# TSL2561_Luminosity_Sensor_Breakout_V01.net
KiCad netlist of a schematic drawn in EAGLE
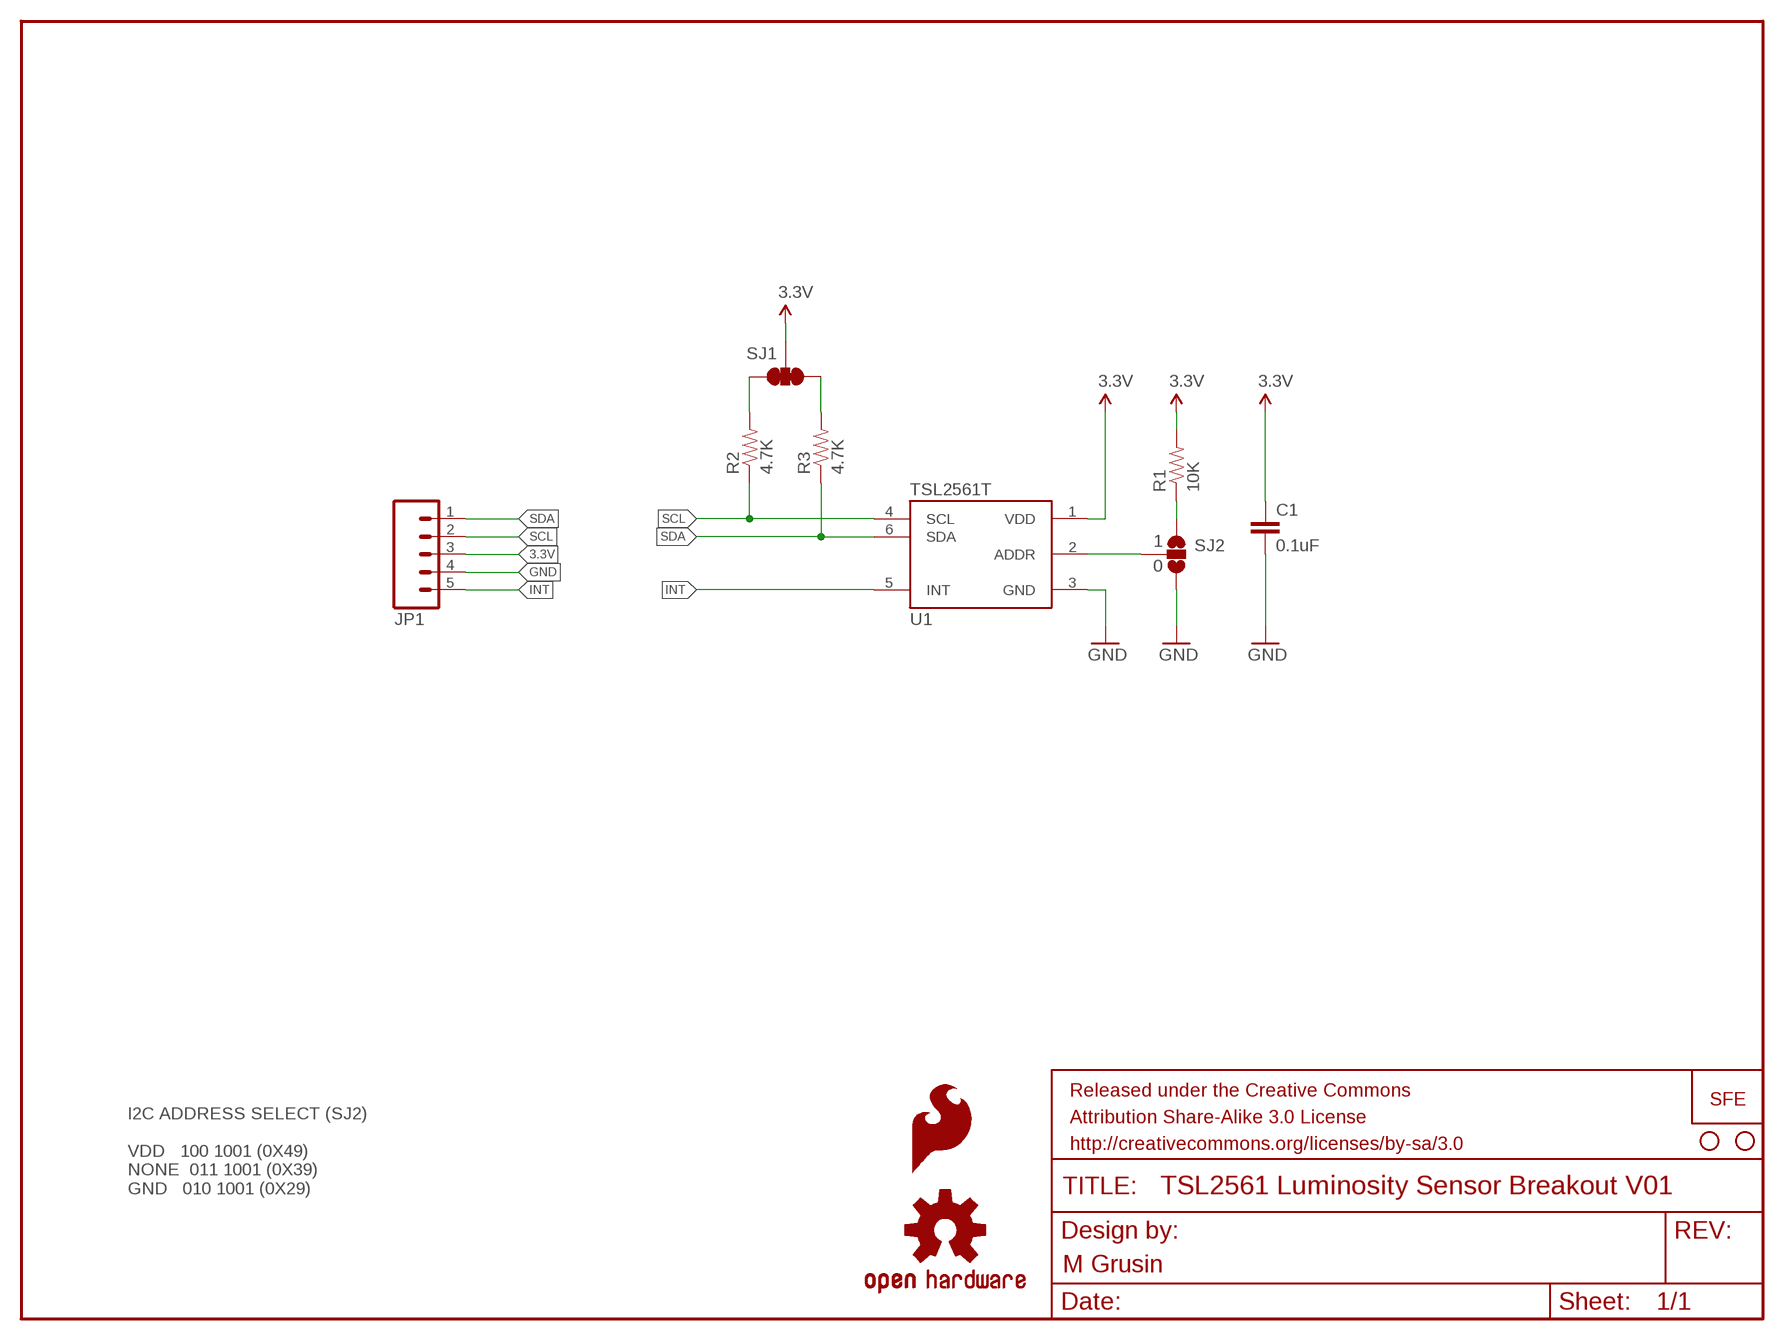
[diagram p0: schematic, sheet 1]

(export (version "E")
  (design (tool "Eeschema 10.0.6"))
  (components
    (comp (ref "C1")
      (value "0.1uF")
      (footprint "eagle-import:0603-CAP")
      (libsource (lib "eagle-import") (part "CAP0603-CAP"))
    )
    (comp (ref "FRAME1")
      (value "FRAME-LETTER")
      (footprint "eagle-import:CREATIVE_COMMONS")
      (libsource (lib "eagle-import") (part "FRAME-LETTER"))
    )
    (comp (ref "JP1")
      (value "M05_ROUNDONLY_NOSILK")
      (footprint "eagle-import:1X05_ROUNDONLY_NOSILK")
      (libsource (lib "eagle-import") (part "M05_ROUNDONLY_NOSILK"))
    )
    (comp (ref "LOGO1")
      (value "OSHW-LOGOS")
      (footprint "eagle-import:OSHW-LOGO-S")
      (libsource (lib "eagle-import") (part "OSHW-LOGOS"))
    )
    (comp (ref "LOGO2")
      (value "LOGO-SFENW2")
      (footprint "eagle-import:SFE-NEW-WEB")
      (libsource (lib "eagle-import") (part "LOGO-SFENW2"))
    )
    (comp (ref "LOGO3")
      (value "SFE_LOGO_FLAME.1_INCH")
      (footprint "eagle-import:SFE_LOGO_FLAME_.1")
      (libsource (lib "eagle-import") (part "SFE_LOGO_FLAME.1_INCH"))
    )
    (comp (ref "R1")
      (value "10K")
      (footprint "eagle-import:0603-RES")
      (libsource (lib "eagle-import") (part "RESISTOR0603"))
    )
    (comp (ref "R2")
      (value "4.7K")
      (footprint "eagle-import:0603-RES")
      (libsource (lib "eagle-import") (part "RESISTOR0603"))
    )
    (comp (ref "R3")
      (value "4.7K")
      (footprint "eagle-import:0603-RES")
      (libsource (lib "eagle-import") (part "RESISTOR0603"))
    )
    (comp (ref "SJ1")
      (value "SOLDERJUMPER_2WAYPASTE1&2&3")
      (footprint "eagle-import:SJ_3_PASTE1&2&3")
      (libsource (lib "eagle-import") (part "SOLDERJUMPER_2WAYPASTE1&2&3"))
    )
    (comp (ref "SJ2")
      (value "SOLDERJUMPER_2WAYS")
      (footprint "eagle-import:SJ_3")
      (libsource (lib "eagle-import") (part "SOLDERJUMPER_2WAYS"))
    )
    (comp (ref "STANDOFF1")
      (value "STAND-OFF")
      (footprint "eagle-import:STAND-OFF")
      (libsource (lib "eagle-import") (part "STAND-OFF"))
    )
    (comp (ref "STANDOFF2")
      (value "STAND-OFF")
      (footprint "eagle-import:STAND-OFF")
      (libsource (lib "eagle-import") (part "STAND-OFF"))
    )
    (comp (ref "U1")
      (value "TSL2561T")
      (footprint "eagle-import:TMB-6")
      (libsource (lib "eagle-import") (part "TSL2561T"))
    )
  )
  (nets
    (net (code "1") (name "3.3V") (class "Default")
      (node (ref "C1") (pin "1") (pinfunction "1_1") (pintype "passive"))
      (node (ref "JP1") (pin "3") (pinfunction "3_3") (pintype "passive"))
      (node (ref "R1") (pin "2") (pinfunction "2_2") (pintype "passive"))
      (node (ref "SJ1") (pin "2") (pinfunction "2_2") (pintype "passive"))
      (node (ref "U1") (pin "1") (pinfunction "VDD_1") (pintype "power_in"))
    )
    (net (code "2") (name "GND") (class "Default")
      (node (ref "C1") (pin "2") (pinfunction "2_2") (pintype "passive"))
      (node (ref "JP1") (pin "4") (pinfunction "4_4") (pintype "passive"))
      (node (ref "SJ2") (pin "3") (pinfunction "3_3") (pintype "passive"))
      (node (ref "U1") (pin "3") (pinfunction "GND_3") (pintype "power_in"))
    )
    (net (code "3") (name "INT") (class "Default")
      (node (ref "JP1") (pin "5") (pinfunction "5_5") (pintype "passive"))
      (node (ref "U1") (pin "5") (pinfunction "INT_5") (pintype "output"))
    )
    (net (code "4") (name "Net-(R1-Pad1)") (class "Default")
      (node (ref "R1") (pin "1") (pinfunction "1_1") (pintype "passive"))
      (node (ref "SJ2") (pin "1") (pinfunction "1_1") (pintype "passive"))
    )
    (net (code "5") (name "Net-(R2-Pad2)") (class "Default")
      (node (ref "R2") (pin "2") (pinfunction "2_2") (pintype "passive"))
      (node (ref "SJ1") (pin "3") (pinfunction "3_3") (pintype "passive"))
    )
    (net (code "6") (name "Net-(R3-Pad2)") (class "Default")
      (node (ref "R3") (pin "2") (pinfunction "2_2") (pintype "passive"))
      (node (ref "SJ1") (pin "1") (pinfunction "1_1") (pintype "passive"))
    )
    (net (code "7") (name "Net-(U1-ADDR)") (class "Default")
      (node (ref "SJ2") (pin "2") (pinfunction "2_2") (pintype "passive"))
      (node (ref "U1") (pin "2") (pinfunction "ADDR_2") (pintype "input"))
    )
    (net (code "8") (name "SCL") (class "Default")
      (node (ref "JP1") (pin "2") (pinfunction "2_2") (pintype "passive"))
      (node (ref "R2") (pin "1") (pinfunction "1_1") (pintype "passive"))
      (node (ref "U1") (pin "4") (pinfunction "SCL_4") (pintype "input"))
    )
    (net (code "9") (name "SDA") (class "Default")
      (node (ref "JP1") (pin "1") (pinfunction "1_1") (pintype "passive"))
      (node (ref "R3") (pin "1") (pinfunction "1_1") (pintype "passive"))
      (node (ref "U1") (pin "6") (pinfunction "SDA_6") (pintype "bidirectional"))
    )
  )
)
